# sx1509-breakout_mount_remap4.net
KiCad netlist of a schematic drawn in EAGLE
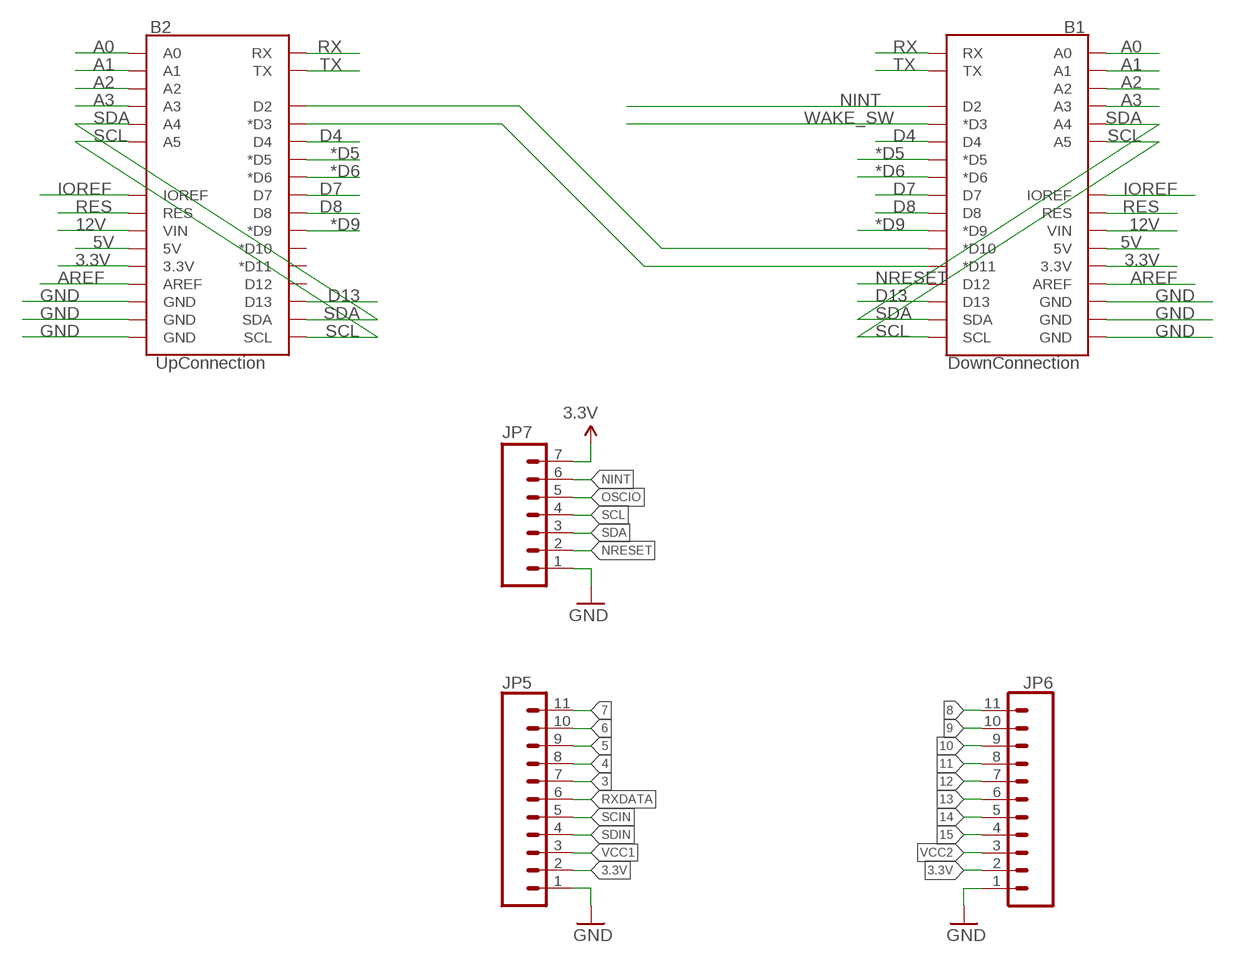
[diagram p0: schematic, sheet 1, part 1 of 2]
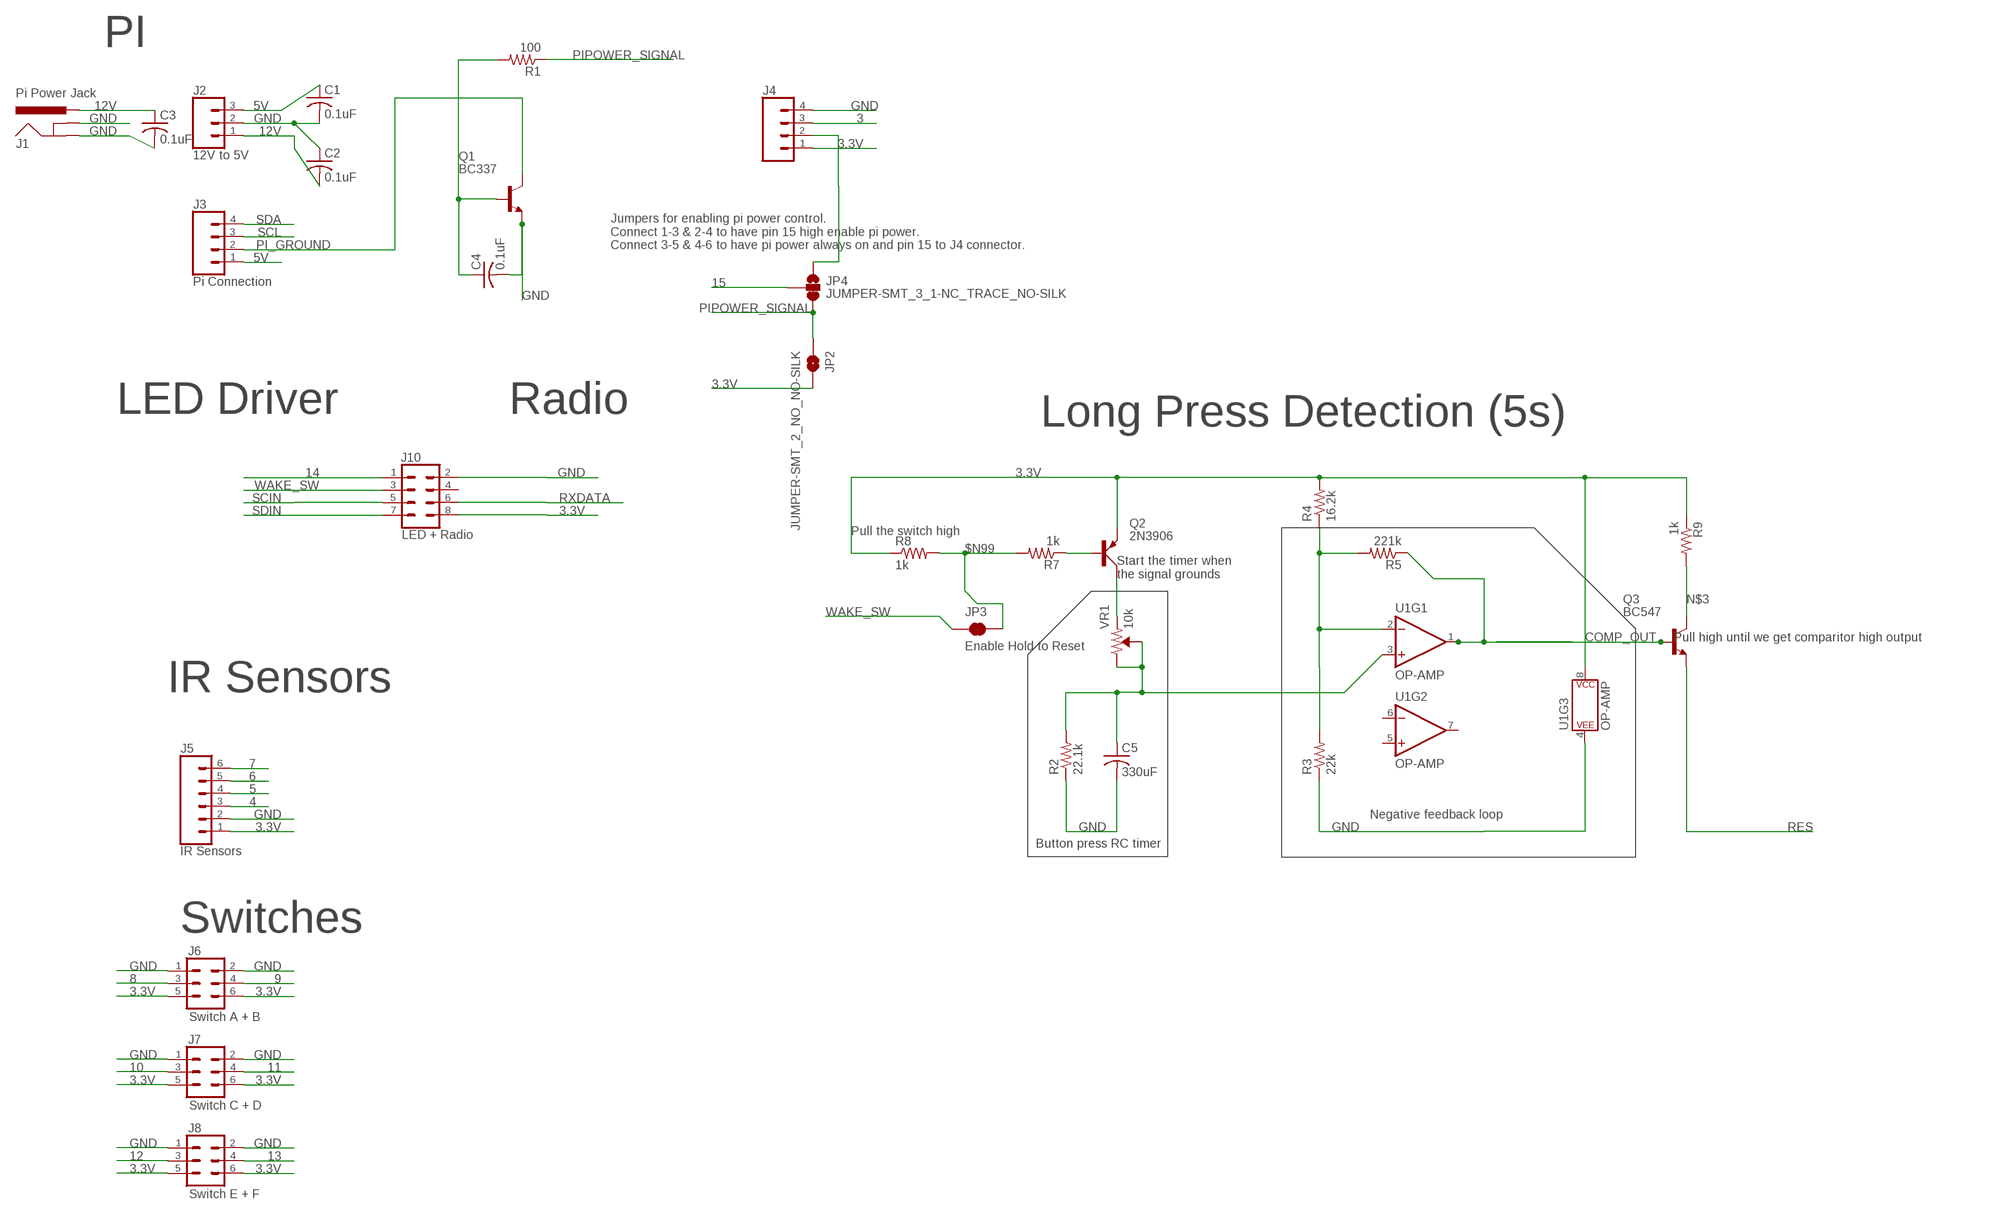
[diagram p1: schematic, sheet 1, part 2 of 2]

(export (version "E")
  (design (tool "Eeschema 10.0.6"))
  (components
    (comp (ref "B1")
      (value "DownConnection")
      (footprint "eagle-import:UNO_R3_SHIELD_NOLABELS")
      (libsource (lib "eagle-import") (part "ARDUINO_UNO_R3_SHIELDNOLABELS"))
    )
    (comp (ref "B2")
      (value "UpConnection")
      (footprint "eagle-import:UNO_R3_SHIELD_NOLABELS")
      (libsource (lib "eagle-import") (part "ARDUINO_UNO_R3_SHIELDNOLABELS"))
    )
    (comp (ref "C1")
      (value "0.1uF")
      (footprint "eagle-import:C0805")
      (libsource (lib "eagle-import") (part "C-USC0805"))
    )
    (comp (ref "C2")
      (value "0.1uF")
      (footprint "eagle-import:C0805")
      (libsource (lib "eagle-import") (part "C-USC0805"))
    )
    (comp (ref "C3")
      (value "0.1uF")
      (footprint "eagle-import:C0805")
      (libsource (lib "eagle-import") (part "C-USC0805"))
    )
    (comp (ref "C4")
      (value "0.1uF")
      (footprint "eagle-import:C0805")
      (libsource (lib "eagle-import") (part "C-USC0805"))
    )
    (comp (ref "C5")
      (value "330uF")
      (footprint "eagle-import:C0805")
      (libsource (lib "eagle-import") (part "C-USC0805"))
    )
    (comp (ref "J1")
      (value "Pi Power Jack")
      (footprint "eagle-import:POWER_JACK_PTH_BREAD")
      (libsource (lib "eagle-import") (part "POWER_JACKPTH_BREAD"))
    )
    (comp (ref "J2")
      (value "12V to 5V")
      (footprint "eagle-import:1X03")
      (libsource (lib "eagle-import") (part "CONN_03"))
    )
    (comp (ref "J3")
      (value "Pi Connection")
      (footprint "eagle-import:1X04")
      (libsource (lib "eagle-import") (part "CONN_04"))
    )
    (comp (ref "J4")
      (value "CONN_04")
      (footprint "eagle-import:1X04")
      (libsource (lib "eagle-import") (part "CONN_04"))
    )
    (comp (ref "J5")
      (value "IR Sensors")
      (footprint "eagle-import:1X06")
      (libsource (lib "eagle-import") (part "CONN_06SILK_FEMALE_PTH"))
    )
    (comp (ref "J6")
      (value "Switch A + B")
      (footprint "eagle-import:2X3")
      (libsource (lib "eagle-import") (part "CONN_03X2FEMALE"))
    )
    (comp (ref "J7")
      (value "Switch C + D")
      (footprint "eagle-import:2X3")
      (libsource (lib "eagle-import") (part "CONN_03X2FEMALE"))
    )
    (comp (ref "J8")
      (value "Switch E + F")
      (footprint "eagle-import:2X3")
      (libsource (lib "eagle-import") (part "CONN_03X2FEMALE"))
    )
    (comp (ref "J10")
      (value "LED + Radio")
      (footprint "eagle-import:2X4")
      (libsource (lib "eagle-import") (part "CONN_04X2"))
    )
    (comp (ref "JP2")
      (value "JUMPER-SMT_2_NO_NO-SILK")
      (footprint "eagle-import:SMT-JUMPER_2_NO_NO-SILK")
      (libsource (lib "eagle-import") (part "JUMPER-SMT_2_NO_NO-SILK"))
    )
    (comp (ref "JP3")
      (value "Enable Hold to Reset")
      (footprint "eagle-import:SMT-JUMPER_2_NC_TRACE_SILK")
      (libsource (lib "eagle-import") (part "JUMPER-SMT_2_NC_TRACE_SILK"))
    )
    (comp (ref "JP4")
      (value "JUMPER-SMT_3_1-NC_TRACE_NO-SILK")
      (footprint "eagle-import:SMT-JUMPER_3_1-NC_TRACE_NO-SILK")
      (libsource (lib "eagle-import") (part "JUMPER-SMT_3_1-NC_TRACE_NO-SILK"))
    )
    (comp (ref "JP5")
      (value "CONN_11")
      (footprint "eagle-import:1X11")
      (libsource (lib "eagle-import") (part "CONN_11"))
    )
    (comp (ref "JP6")
      (value "CONN_11")
      (footprint "eagle-import:1X11")
      (libsource (lib "eagle-import") (part "CONN_11"))
    )
    (comp (ref "JP7")
      (value "M07")
      (footprint "eagle-import:1X07")
      (libsource (lib "eagle-import") (part "M07"))
    )
    (comp (ref "Q1")
      (value "BC337")
      (footprint "eagle-import:TO92")
      (libsource (lib "eagle-import") (part "BC337"))
    )
    (comp (ref "Q2")
      (value "2N3906")
      (footprint "eagle-import:TO92D")
      (libsource (lib "eagle-import") (part "2N3906"))
    )
    (comp (ref "Q3")
      (value "BC547")
      (footprint "eagle-import:TO92")
      (fields (field (name "NOTE") "Pull high until we get comparitor high output"))
      (libsource (lib "eagle-import") (part "BC547"))
    )
    (comp (ref "R1")
      (value "100")
      (footprint "eagle-import:R0805")
      (libsource (lib "eagle-import") (part "R-US_R0805"))
    )
    (comp (ref "R2")
      (value "22.1k")
      (footprint "eagle-import:R0805")
      (libsource (lib "eagle-import") (part "R-US_R0805"))
    )
    (comp (ref "R3")
      (value "22k")
      (footprint "eagle-import:R0805")
      (libsource (lib "eagle-import") (part "R-US_R0805"))
    )
    (comp (ref "R4")
      (value "16.2k")
      (footprint "eagle-import:R0805")
      (libsource (lib "eagle-import") (part "R-US_R0805"))
    )
    (comp (ref "R5")
      (value "221k")
      (footprint "eagle-import:R0805")
      (libsource (lib "eagle-import") (part "R-US_R0805"))
    )
    (comp (ref "R7")
      (value "1k")
      (footprint "eagle-import:R0805")
      (libsource (lib "eagle-import") (part "R-US_R0805"))
    )
    (comp (ref "R8")
      (value "1k")
      (footprint "eagle-import:R0805")
      (fields (field (name "NOTE") "Pull the switch high"))
      (libsource (lib "eagle-import") (part "R-US_R0805"))
    )
    (comp (ref "R9")
      (value "1k")
      (footprint "eagle-import:R0805")
      (libsource (lib "eagle-import") (part "R-US_R0805"))
    )
    (comp (ref "U1")
      (value "OP-AMP")
      (footprint "eagle-import:SO08")
      (libsource (lib "eagle-import") (part "OPAMP-DUALU"))
    )
    (comp (ref "VR1")
      (value "10k")
      (footprint "eagle-import:TRIMPOT-PTH-3386U")
      (libsource (lib "eagle-import") (part "TRIMPOT-PTH-10MM-KNOB-1/2W-10%"))
    )
  )
  (nets
    (net (code "1") (name "/$N99") (class "Default")
      (node (ref "JP3") (pin "2") (pinfunction "2_2") (pintype "passive"))
      (node (ref "R7") (pin "2") (pinfunction "2_2") (pintype "passive"))
      (node (ref "R8") (pin "2") (pinfunction "2_2") (pintype "passive"))
    )
    (net (code "2") (name "/*D5") (class "Default")
      (node (ref "B1") (pin "D5") (pinfunction "*D5_D5") (pintype "bidirectional"))
      (node (ref "B2") (pin "D5") (pinfunction "*D5_D5") (pintype "bidirectional"))
    )
    (net (code "3") (name "/*D6") (class "Default")
      (node (ref "B1") (pin "D6") (pinfunction "*D6_D6") (pintype "bidirectional"))
      (node (ref "B2") (pin "D6") (pinfunction "*D6_D6") (pintype "bidirectional"))
    )
    (net (code "4") (name "/*D9") (class "Default")
      (node (ref "B1") (pin "D9") (pinfunction "*D9_D9") (pintype "bidirectional"))
      (node (ref "B2") (pin "D9") (pinfunction "*D9_D9") (pintype "bidirectional"))
    )
    (net (code "5") (name "/5V") (class "Default")
      (node (ref "B1") (pin "5V") (pinfunction "5V_5V") (pintype "bidirectional"))
      (node (ref "B2") (pin "5V") (pinfunction "5V_5V") (pintype "bidirectional"))
      (node (ref "C1") (pin "1") (pinfunction "1_1") (pintype "passive"))
      (node (ref "J2") (pin "3") (pinfunction "3_3") (pintype "passive"))
      (node (ref "J3") (pin "1") (pinfunction "1_1") (pintype "passive"))
    )
    (net (code "6") (name "/12V") (class "Default")
      (node (ref "B1") (pin "VIN") (pinfunction "VIN_VIN") (pintype "bidirectional"))
      (node (ref "B2") (pin "VIN") (pinfunction "VIN_VIN") (pintype "bidirectional"))
      (node (ref "C2") (pin "2") (pinfunction "2_2") (pintype "passive"))
      (node (ref "C3") (pin "1") (pinfunction "1_1") (pintype "passive"))
      (node (ref "J1") (pin "PWR") (pinfunction "PWR_PWR") (pintype "bidirectional"))
      (node (ref "J2") (pin "1") (pinfunction "1_1") (pintype "passive"))
    )
    (net (code "7") (name "/A0") (class "Default")
      (node (ref "B1") (pin "A0") (pinfunction "A0_A0") (pintype "bidirectional"))
      (node (ref "B2") (pin "A0") (pinfunction "A0_A0") (pintype "bidirectional"))
    )
    (net (code "8") (name "/A1") (class "Default")
      (node (ref "B1") (pin "A1") (pinfunction "A1_A1") (pintype "bidirectional"))
      (node (ref "B2") (pin "A1") (pinfunction "A1_A1") (pintype "bidirectional"))
    )
    (net (code "9") (name "/A2") (class "Default")
      (node (ref "B1") (pin "A2") (pinfunction "A2_A2") (pintype "bidirectional"))
      (node (ref "B2") (pin "A2") (pinfunction "A2_A2") (pintype "bidirectional"))
    )
    (net (code "10") (name "/A3") (class "Default")
      (node (ref "B1") (pin "A3") (pinfunction "A3_A3") (pintype "bidirectional"))
      (node (ref "B2") (pin "A3") (pinfunction "A3_A3") (pintype "bidirectional"))
    )
    (net (code "11") (name "/AREF") (class "Default")
      (node (ref "B1") (pin "AREF") (pinfunction "AREF_AREF") (pintype "bidirectional"))
      (node (ref "B2") (pin "AREF") (pinfunction "AREF_AREF") (pintype "bidirectional"))
    )
    (net (code "12") (name "/COMP_OUT") (class "Default")
      (node (ref "Q3") (pin "2") (pinfunction "B_2") (pintype "passive"))
      (node (ref "R5") (pin "1") (pinfunction "1_1") (pintype "passive"))
      (node (ref "U1") (pin "1") (pinfunction "OUT_1") (pintype "output"))
    )
    (net (code "13") (name "/D4") (class "Default")
      (node (ref "B1") (pin "D4") (pinfunction "D4_D4") (pintype "bidirectional"))
      (node (ref "B2") (pin "D4") (pinfunction "D4_D4") (pintype "bidirectional"))
    )
    (net (code "14") (name "/D7") (class "Default")
      (node (ref "B1") (pin "D7") (pinfunction "D7_D7") (pintype "bidirectional"))
      (node (ref "B2") (pin "D7") (pinfunction "D7_D7") (pintype "bidirectional"))
    )
    (net (code "15") (name "/D8") (class "Default")
      (node (ref "B1") (pin "D8") (pinfunction "D8_D8") (pintype "bidirectional"))
      (node (ref "B2") (pin "D8") (pinfunction "D8_D8") (pintype "bidirectional"))
    )
    (net (code "16") (name "/D13") (class "Default")
      (node (ref "B1") (pin "D13") (pinfunction "D13_D13") (pintype "bidirectional"))
      (node (ref "B2") (pin "D13") (pinfunction "D13_D13") (pintype "bidirectional"))
    )
    (net (code "17") (name "/IOREF") (class "Default")
      (node (ref "B1") (pin "IOREF") (pinfunction "IOREF_IOREF") (pintype "bidirectional"))
      (node (ref "B2") (pin "IOREF") (pinfunction "IOREF_IOREF") (pintype "bidirectional"))
    )
    (net (code "18") (name "/N$3") (class "Default")
      (node (ref "Q3") (pin "3") (pinfunction "C_3") (pintype "passive"))
      (node (ref "R9") (pin "2") (pinfunction "2_2") (pintype "passive"))
    )
    (net (code "19") (name "/PIPOWER_SIGNAL") (class "Default")
      (node (ref "JP2") (pin "1") (pinfunction "1_1") (pintype "passive"))
      (node (ref "JP4") (pin "3") (pinfunction "3_3") (pintype "passive"))
      (node (ref "R1") (pin "1") (pinfunction "1_1") (pintype "passive"))
    )
    (net (code "20") (name "/PI_GROUND") (class "Default")
      (node (ref "J3") (pin "2") (pinfunction "2_2") (pintype "passive"))
      (node (ref "Q1") (pin "3") (pinfunction "C_3") (pintype "passive"))
    )
    (net (code "21") (name "/RES") (class "Default")
      (node (ref "B1") (pin "RES") (pinfunction "RES_RES") (pintype "bidirectional"))
      (node (ref "B2") (pin "RES") (pinfunction "RES_RES") (pintype "bidirectional"))
      (node (ref "Q3") (pin "1") (pinfunction "E_1") (pintype "passive"))
    )
    (net (code "22") (name "/RX") (class "Default")
      (node (ref "B1") (pin "RX") (pinfunction "RX_RX") (pintype "bidirectional"))
      (node (ref "B2") (pin "RX") (pinfunction "RX_RX") (pintype "bidirectional"))
    )
    (net (code "23") (name "/TX") (class "Default")
      (node (ref "B1") (pin "TX") (pinfunction "TX_TX") (pintype "bidirectional"))
      (node (ref "B2") (pin "TX") (pinfunction "TX_TX") (pintype "bidirectional"))
    )
    (net (code "24") (name "/WAKE_SW") (class "Default")
      (node (ref "B1") (pin "D3") (pinfunction "*D3_D3") (pintype "bidirectional"))
      (node (ref "J10") (pin "3") (pinfunction "3_3") (pintype "passive"))
      (node (ref "JP3") (pin "1") (pinfunction "1_1") (pintype "passive"))
    )
    (net (code "25") (name "3") (class "Default")
      (node (ref "J4") (pin "3") (pinfunction "3_3") (pintype "passive"))
      (node (ref "JP5") (pin "7") (pinfunction "7_7") (pintype "passive"))
    )
    (net (code "26") (name "3.3V") (class "Default")
      (node (ref "B1") (pin "3.3V") (pinfunction "3.3V_3.3V") (pintype "bidirectional"))
      (node (ref "B2") (pin "3.3V") (pinfunction "3.3V_3.3V") (pintype "bidirectional"))
      (node (ref "J10") (pin "8") (pinfunction "8_8") (pintype "passive"))
      (node (ref "J4") (pin "1") (pinfunction "1_1") (pintype "passive"))
      (node (ref "J5") (pin "1") (pinfunction "1_1") (pintype "passive"))
      (node (ref "J6") (pin "5") (pinfunction "5_5") (pintype "bidirectional"))
      (node (ref "J6") (pin "6") (pinfunction "6_6") (pintype "bidirectional"))
      (node (ref "J7") (pin "5") (pinfunction "5_5") (pintype "bidirectional"))
      (node (ref "J7") (pin "6") (pinfunction "6_6") (pintype "bidirectional"))
      (node (ref "J8") (pin "5") (pinfunction "5_5") (pintype "bidirectional"))
      (node (ref "J8") (pin "6") (pinfunction "6_6") (pintype "bidirectional"))
      (node (ref "JP2") (pin "2") (pinfunction "2_2") (pintype "passive"))
      (node (ref "JP5") (pin "2") (pinfunction "2_2") (pintype "passive"))
      (node (ref "JP6") (pin "2") (pinfunction "2_2") (pintype "passive"))
      (node (ref "JP7") (pin "7") (pinfunction "7_7") (pintype "passive"))
      (node (ref "Q2") (pin "E") (pinfunction "E_E") (pintype "passive"))
      (node (ref "R4") (pin "2") (pinfunction "2_2") (pintype "passive"))
      (node (ref "R8") (pin "1") (pinfunction "1_1") (pintype "passive"))
      (node (ref "R9") (pin "1") (pinfunction "1_1") (pintype "passive"))
      (node (ref "U1") (pin "8") (pinfunction "P$V+_8") (pintype "bidirectional"))
    )
    (net (code "27") (name "4") (class "Default")
      (node (ref "J5") (pin "3") (pinfunction "3_3") (pintype "passive"))
      (node (ref "JP5") (pin "8") (pinfunction "8_8") (pintype "passive"))
    )
    (net (code "28") (name "5") (class "Default")
      (node (ref "J5") (pin "4") (pinfunction "4_4") (pintype "passive"))
      (node (ref "JP5") (pin "9") (pinfunction "9_9") (pintype "passive"))
    )
    (net (code "29") (name "6") (class "Default")
      (node (ref "J5") (pin "5") (pinfunction "5_5") (pintype "passive"))
      (node (ref "JP5") (pin "10") (pinfunction "10_10") (pintype "passive"))
    )
    (net (code "30") (name "7") (class "Default")
      (node (ref "J5") (pin "6") (pinfunction "6_6") (pintype "passive"))
      (node (ref "JP5") (pin "11") (pinfunction "11_11") (pintype "passive"))
    )
    (net (code "31") (name "8") (class "Default")
      (node (ref "J6") (pin "3") (pinfunction "3_3") (pintype "bidirectional"))
      (node (ref "JP6") (pin "11") (pinfunction "11_11") (pintype "passive"))
    )
    (net (code "32") (name "9") (class "Default")
      (node (ref "J6") (pin "4") (pinfunction "4_4") (pintype "bidirectional"))
      (node (ref "JP6") (pin "10") (pinfunction "10_10") (pintype "passive"))
    )
    (net (code "33") (name "10") (class "Default")
      (node (ref "J7") (pin "3") (pinfunction "3_3") (pintype "bidirectional"))
      (node (ref "JP6") (pin "9") (pinfunction "9_9") (pintype "passive"))
    )
    (net (code "34") (name "11") (class "Default")
      (node (ref "J7") (pin "4") (pinfunction "4_4") (pintype "bidirectional"))
      (node (ref "JP6") (pin "8") (pinfunction "8_8") (pintype "passive"))
    )
    (net (code "35") (name "12") (class "Default")
      (node (ref "J8") (pin "3") (pinfunction "3_3") (pintype "bidirectional"))
      (node (ref "JP6") (pin "7") (pinfunction "7_7") (pintype "passive"))
    )
    (net (code "36") (name "13") (class "Default")
      (node (ref "J8") (pin "4") (pinfunction "4_4") (pintype "bidirectional"))
      (node (ref "JP6") (pin "6") (pinfunction "6_6") (pintype "passive"))
    )
    (net (code "37") (name "14") (class "Default")
      (node (ref "J10") (pin "1") (pinfunction "1_1") (pintype "passive"))
      (node (ref "JP6") (pin "5") (pinfunction "5_5") (pintype "passive"))
    )
    (net (code "38") (name "15") (class "Default")
      (node (ref "JP4") (pin "2") (pinfunction "2_2") (pintype "passive"))
      (node (ref "JP6") (pin "4") (pinfunction "4_4") (pintype "passive"))
    )
    (net (code "39") (name "GND") (class "Default")
      (node (ref "B1") (pin "GND@0") (pinfunction "GND_GND@0") (pintype "bidirectional"))
      (node (ref "B1") (pin "GND@1") (pinfunction "GND_GND@1") (pintype "bidirectional"))
      (node (ref "B1") (pin "GND@2") (pinfunction "GND_GND@2") (pintype "bidirectional"))
      (node (ref "B2") (pin "GND@0") (pinfunction "GND_GND@0") (pintype "bidirectional"))
      (node (ref "B2") (pin "GND@1") (pinfunction "GND_GND@1") (pintype "bidirectional"))
      (node (ref "B2") (pin "GND@2") (pinfunction "GND_GND@2") (pintype "bidirectional"))
      (node (ref "C1") (pin "2") (pinfunction "2_2") (pintype "passive"))
      (node (ref "C2") (pin "1") (pinfunction "1_1") (pintype "passive"))
      (node (ref "C3") (pin "2") (pinfunction "2_2") (pintype "passive"))
      (node (ref "C4") (pin "2") (pinfunction "2_2") (pintype "passive"))
      (node (ref "C5") (pin "2") (pinfunction "2_2") (pintype "passive"))
      (node (ref "J1") (pin "GND") (pinfunction "GND_GND") (pintype "bidirectional"))
      (node (ref "J1") (pin "GNDBREAK") (pinfunction "GNDBREAK_GNDBREAK") (pintype "bidirectional"))
      (node (ref "J10") (pin "2") (pinfunction "2_2") (pintype "passive"))
      (node (ref "J2") (pin "2") (pinfunction "2_2") (pintype "passive"))
      (node (ref "J4") (pin "4") (pinfunction "4_4") (pintype "passive"))
      (node (ref "J5") (pin "2") (pinfunction "2_2") (pintype "passive"))
      (node (ref "J6") (pin "1") (pinfunction "1_1") (pintype "bidirectional"))
      (node (ref "J6") (pin "2") (pinfunction "2_2") (pintype "bidirectional"))
      (node (ref "J7") (pin "1") (pinfunction "1_1") (pintype "bidirectional"))
      (node (ref "J7") (pin "2") (pinfunction "2_2") (pintype "bidirectional"))
      (node (ref "J8") (pin "1") (pinfunction "1_1") (pintype "bidirectional"))
      (node (ref "J8") (pin "2") (pinfunction "2_2") (pintype "bidirectional"))
      (node (ref "JP5") (pin "1") (pinfunction "1_1") (pintype "passive"))
      (node (ref "JP6") (pin "1") (pinfunction "1_1") (pintype "passive"))
      (node (ref "JP7") (pin "1") (pinfunction "1_1") (pintype "passive"))
      (node (ref "Q1") (pin "1") (pinfunction "E_1") (pintype "passive"))
      (node (ref "R2") (pin "1") (pinfunction "1_1") (pintype "passive"))
      (node (ref "R3") (pin "1") (pinfunction "1_1") (pintype "passive"))
      (node (ref "U1") (pin "4") (pinfunction "P$V-_4") (pintype "bidirectional"))
    )
    (net (code "40") (name "NINT") (class "Default")
      (node (ref "B1") (pin "D2") (pinfunction "D2_D2") (pintype "bidirectional"))
      (node (ref "JP7") (pin "6") (pinfunction "6_6") (pintype "passive"))
    )
    (net (code "41") (name "NRESET") (class "Default")
      (node (ref "B1") (pin "D12") (pinfunction "D12_D12") (pintype "bidirectional"))
      (node (ref "JP7") (pin "2") (pinfunction "2_2") (pintype "passive"))
    )
    (net (code "42") (name "Net-(B1-*D10)") (class "Default")
      (node (ref "B1") (pin "D10") (pinfunction "*D10_D10") (pintype "bidirectional"))
      (node (ref "B2") (pin "D2") (pinfunction "D2_D2") (pintype "bidirectional"))
    )
    (net (code "43") (name "Net-(B1-*D11)") (class "Default")
      (node (ref "B1") (pin "D11") (pinfunction "*D11_D11") (pintype "bidirectional"))
      (node (ref "B2") (pin "D3") (pinfunction "*D3_D3") (pintype "bidirectional"))
    )
    (net (code "44") (name "Net-(J4-Pad2)") (class "Default")
      (node (ref "J4") (pin "2") (pinfunction "2_2") (pintype "passive"))
      (node (ref "JP4") (pin "1") (pinfunction "1_1") (pintype "passive"))
    )
    (net (code "45") (name "Net-(Q1-B)") (class "Default")
      (node (ref "C4") (pin "1") (pinfunction "1_1") (pintype "passive"))
      (node (ref "Q1") (pin "2") (pinfunction "B_2") (pintype "passive"))
      (node (ref "R1") (pin "2") (pinfunction "2_2") (pintype "passive"))
    )
    (net (code "46") (name "Net-(Q2-PadB)") (class "Default")
      (node (ref "Q2") (pin "B") (pinfunction "B_B") (pintype "passive"))
      (node (ref "R7") (pin "1") (pinfunction "1_1") (pintype "passive"))
    )
    (net (code "47") (name "Net-(U1A-+IN)") (class "Default")
      (node (ref "C5") (pin "1") (pinfunction "1_1") (pintype "passive"))
      (node (ref "R2") (pin "2") (pinfunction "2_2") (pintype "passive"))
      (node (ref "U1") (pin "3") (pinfunction "+IN_3") (pintype "input"))
      (node (ref "VR1") (pin "2") (pinfunction "WIPER_2") (pintype "passive"))
      (node (ref "VR1") (pin "3") (pinfunction "CW_3") (pintype "passive"))
    )
    (net (code "48") (name "Net-(U1A--IN)") (class "Default")
      (node (ref "R3") (pin "2") (pinfunction "2_2") (pintype "passive"))
      (node (ref "R4") (pin "1") (pinfunction "1_1") (pintype "passive"))
      (node (ref "R5") (pin "2") (pinfunction "2_2") (pintype "passive"))
      (node (ref "U1") (pin "2") (pinfunction "-IN_2") (pintype "input"))
    )
    (net (code "49") (name "Net-(VR1-CCW)") (class "Default")
      (node (ref "Q2") (pin "C") (pinfunction "C_C") (pintype "passive"))
      (node (ref "VR1") (pin "1") (pinfunction "CCW_1") (pintype "passive"))
    )
    (net (code "50") (name "OSCIO") (class "Default")
      (node (ref "JP7") (pin "5") (pinfunction "5_5") (pintype "passive"))
    )
    (net (code "51") (name "RXDATA") (class "Default")
      (node (ref "J10") (pin "6") (pinfunction "6_6") (pintype "passive"))
      (node (ref "JP5") (pin "6") (pinfunction "6_6") (pintype "passive"))
    )
    (net (code "52") (name "SCIN") (class "Default")
      (node (ref "J10") (pin "5") (pinfunction "5_5") (pintype "passive"))
      (node (ref "JP5") (pin "5") (pinfunction "5_5") (pintype "passive"))
    )
    (net (code "53") (name "SCL") (class "Default")
      (node (ref "B1") (pin "A5") (pinfunction "A5_A5") (pintype "bidirectional"))
      (node (ref "B1") (pin "SCL") (pinfunction "SCL_SCL") (pintype "bidirectional"))
      (node (ref "B2") (pin "A5") (pinfunction "A5_A5") (pintype "bidirectional"))
      (node (ref "B2") (pin "SCL") (pinfunction "SCL_SCL") (pintype "bidirectional"))
      (node (ref "J3") (pin "3") (pinfunction "3_3") (pintype "passive"))
      (node (ref "JP7") (pin "4") (pinfunction "4_4") (pintype "passive"))
    )
    (net (code "54") (name "SDA") (class "Default")
      (node (ref "B1") (pin "A4") (pinfunction "A4_A4") (pintype "bidirectional"))
      (node (ref "B1") (pin "SDA") (pinfunction "SDA_SDA") (pintype "bidirectional"))
      (node (ref "B2") (pin "A4") (pinfunction "A4_A4") (pintype "bidirectional"))
      (node (ref "B2") (pin "SDA") (pinfunction "SDA_SDA") (pintype "bidirectional"))
      (node (ref "J3") (pin "4") (pinfunction "4_4") (pintype "passive"))
      (node (ref "JP7") (pin "3") (pinfunction "3_3") (pintype "passive"))
    )
    (net (code "55") (name "SDIN") (class "Default")
      (node (ref "J10") (pin "7") (pinfunction "7_7") (pintype "passive"))
      (node (ref "JP5") (pin "4") (pinfunction "4_4") (pintype "passive"))
    )
    (net (code "56") (name "VCC1") (class "Default")
      (node (ref "JP5") (pin "3") (pinfunction "3_3") (pintype "passive"))
    )
    (net (code "57") (name "VCC2") (class "Default")
      (node (ref "JP6") (pin "3") (pinfunction "3_3") (pintype "passive"))
    )
    (net (code "58") (name "unconnected-(B2-*D10-PadD10)") (class "Default")
      (node (ref "B2") (pin "D10") (pinfunction "*D10_D10") (pintype "bidirectional"))
    )
    (net (code "59") (name "unconnected-(B2-*D11-PadD11)") (class "Default")
      (node (ref "B2") (pin "D11") (pinfunction "*D11_D11") (pintype "bidirectional"))
    )
    (net (code "60") (name "unconnected-(B2-PadD12)") (class "Default")
      (node (ref "B2") (pin "D12") (pinfunction "D12_D12") (pintype "bidirectional"))
    )
    (net (code "61") (name "unconnected-(J10-Pad4)") (class "Default")
      (node (ref "J10") (pin "4") (pinfunction "4_4") (pintype "passive"))
    )
    (net (code "62") (name "unconnected-(U1B-+IN-Pad5)") (class "Default")
      (node (ref "U1") (pin "5") (pinfunction "+IN_5") (pintype "input"))
    )
    (net (code "63") (name "unconnected-(U1B--IN-Pad6)") (class "Default")
      (node (ref "U1") (pin "6") (pinfunction "-IN_6") (pintype "input"))
    )
    (net (code "64") (name "unconnected-(U1B-OUT-Pad7)") (class "Default")
      (node (ref "U1") (pin "7") (pinfunction "OUT_7") (pintype "output"))
    )
  )
)
